# Encrypter.net
KiCad netlist of a schematic drawn in EAGLE
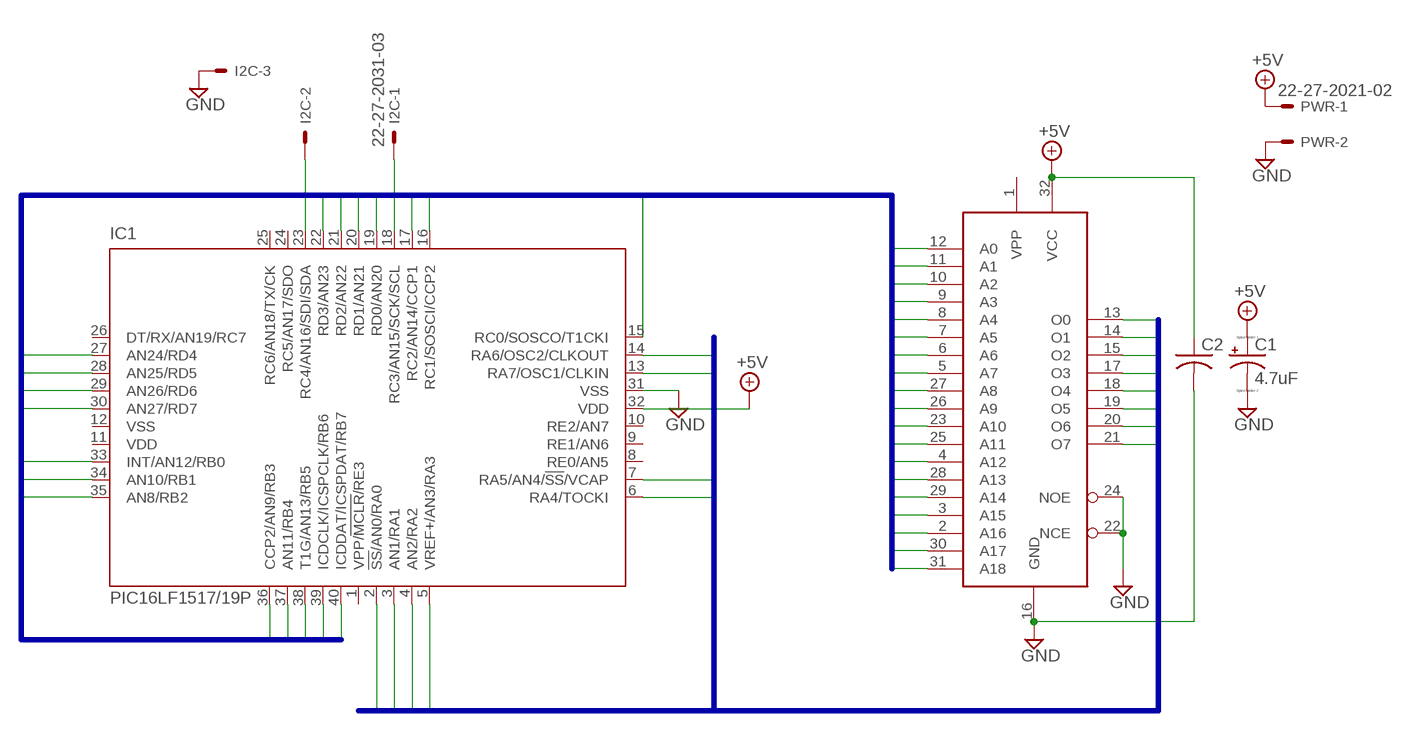
[diagram p0: schematic, sheet 1]

(export (version "E")
  (design (tool "Eeschema 10.0.6"))
  (components
    (comp (ref "C1")
      (value "4.7uF")
      (footprint "eagle-import:E3,5-10")
      (libsource (lib "eagle-import") (part "CPOL-USE3.5-10"))
    )
    (comp (ref "C2")
      (value "C-US050-025X075")
      (footprint "eagle-import:C050-025X075")
      (libsource (lib "eagle-import") (part "C-US050-025X075"))
    )
    (comp (ref "I2C")
      (value "22-27-2031-03")
      (footprint "eagle-import:6410-03")
      (libsource (lib "eagle-import") (part "22-?-0327-2031"))
    )
    (comp (ref "IC1")
      (value "PIC16LF1517/19P")
      (footprint "eagle-import:DIL40")
      (libsource (lib "eagle-import") (part "PIC16F1517/19PL"))
    )
    (comp (ref "PWR")
      (value "22-27-2021-02")
      (footprint "eagle-import:6410-02")
      (libsource (lib "eagle-import") (part "22-?-0227-2021"))
    )
    (comp (ref "U$1")
      (value "AT27C040")
      (footprint "eagle-import:DIL32")
      (libsource (lib "eagle-import") (part "AT27C040"))
    )
  )
  (nets
    (net (code "1") (name "+5V") (class "Default")
      (node (ref "C1") (pin "+") (pinfunction "+_+") (pintype "passive"))
      (node (ref "C2") (pin "1") (pinfunction "1_1") (pintype "passive"))
      (node (ref "IC1") (pin "32") (pinfunction "VDD_32") (pintype "power_in"))
      (node (ref "PWR") (pin "1") (pinfunction "S_1") (pintype "passive"))
      (node (ref "U$1") (pin "32") (pinfunction "VCC_32") (pintype "bidirectional"))
    )
    (net (code "2") (name "/A0") (class "Default")
      (node (ref "IC1") (pin "33") (pinfunction "INT/AN12/RB0_33") (pintype "bidirectional"))
      (node (ref "U$1") (pin "12") (pinfunction "A0_12") (pintype "bidirectional"))
    )
    (net (code "3") (name "/A1") (class "Default")
      (node (ref "IC1") (pin "34") (pinfunction "AN10/RB1_34") (pintype "bidirectional"))
      (node (ref "U$1") (pin "11") (pinfunction "A1_11") (pintype "bidirectional"))
    )
    (net (code "4") (name "/A2") (class "Default")
      (node (ref "IC1") (pin "35") (pinfunction "AN8/RB2_35") (pintype "bidirectional"))
      (node (ref "U$1") (pin "10") (pinfunction "A2_10") (pintype "bidirectional"))
    )
    (net (code "5") (name "/A3") (class "Default")
      (node (ref "IC1") (pin "36") (pinfunction "CCP2/AN9/RB3_36") (pintype "bidirectional"))
      (node (ref "U$1") (pin "9") (pinfunction "A3_9") (pintype "bidirectional"))
    )
    (net (code "6") (name "/A4") (class "Default")
      (node (ref "IC1") (pin "37") (pinfunction "AN11/RB4_37") (pintype "bidirectional"))
      (node (ref "U$1") (pin "8") (pinfunction "A4_8") (pintype "bidirectional"))
    )
    (net (code "7") (name "/A5") (class "Default")
      (node (ref "IC1") (pin "38") (pinfunction "T1G/AN13/RB5_38") (pintype "bidirectional"))
      (node (ref "U$1") (pin "7") (pinfunction "A5_7") (pintype "bidirectional"))
    )
    (net (code "8") (name "/A6") (class "Default")
      (node (ref "IC1") (pin "39") (pinfunction "ICDCLK/ICSPCLK/RB6_39") (pintype "bidirectional"))
      (node (ref "U$1") (pin "6") (pinfunction "A6_6") (pintype "bidirectional"))
    )
    (net (code "9") (name "/A7") (class "Default")
      (node (ref "IC1") (pin "40") (pinfunction "ICDDAT/ICSPDAT/RB7_40") (pintype "bidirectional"))
      (node (ref "U$1") (pin "5") (pinfunction "A7_5") (pintype "bidirectional"))
    )
    (net (code "10") (name "/A8") (class "Default")
      (node (ref "IC1") (pin "15") (pinfunction "RC0/SOSCO/T1CKI_15") (pintype "bidirectional"))
      (node (ref "U$1") (pin "27") (pinfunction "A8_27") (pintype "bidirectional"))
    )
    (net (code "11") (name "/A9") (class "Default")
      (node (ref "IC1") (pin "16") (pinfunction "RC1/SOSCI/CCP2_16") (pintype "bidirectional"))
      (node (ref "U$1") (pin "26") (pinfunction "A9_26") (pintype "bidirectional"))
    )
    (net (code "12") (name "/A10") (class "Default")
      (node (ref "IC1") (pin "17") (pinfunction "RC2/AN14/CCP1_17") (pintype "bidirectional"))
      (node (ref "U$1") (pin "23") (pinfunction "A10_23") (pintype "bidirectional"))
    )
    (net (code "13") (name "/A11") (class "Default")
      (node (ref "IC1") (pin "19") (pinfunction "RD0/AN20_19") (pintype "bidirectional"))
      (node (ref "U$1") (pin "25") (pinfunction "A11_25") (pintype "bidirectional"))
    )
    (net (code "14") (name "/A12") (class "Default")
      (node (ref "IC1") (pin "20") (pinfunction "RD1/AN21_20") (pintype "bidirectional"))
      (node (ref "U$1") (pin "4") (pinfunction "A12_4") (pintype "bidirectional"))
    )
    (net (code "15") (name "/A13") (class "Default")
      (node (ref "IC1") (pin "21") (pinfunction "RD2/AN22_21") (pintype "bidirectional"))
      (node (ref "U$1") (pin "28") (pinfunction "A13_28") (pintype "bidirectional"))
    )
    (net (code "16") (name "/A14") (class "Default")
      (node (ref "IC1") (pin "22") (pinfunction "RD3/AN23_22") (pintype "bidirectional"))
      (node (ref "U$1") (pin "29") (pinfunction "A14_29") (pintype "bidirectional"))
    )
    (net (code "17") (name "/A15") (class "Default")
      (node (ref "IC1") (pin "27") (pinfunction "AN24/RD4_27") (pintype "bidirectional"))
      (node (ref "U$1") (pin "3") (pinfunction "A15_3") (pintype "bidirectional"))
    )
    (net (code "18") (name "/A16") (class "Default")
      (node (ref "IC1") (pin "28") (pinfunction "AN25/RD5_28") (pintype "bidirectional"))
      (node (ref "U$1") (pin "2") (pinfunction "A16_2") (pintype "bidirectional"))
    )
    (net (code "19") (name "/A17") (class "Default")
      (node (ref "IC1") (pin "29") (pinfunction "AN26/RD6_29") (pintype "bidirectional"))
      (node (ref "U$1") (pin "30") (pinfunction "A17_30") (pintype "bidirectional"))
    )
    (net (code "20") (name "/A18") (class "Default")
      (node (ref "IC1") (pin "30") (pinfunction "AN27/RD7_30") (pintype "bidirectional"))
      (node (ref "U$1") (pin "31") (pinfunction "A18_31") (pintype "bidirectional"))
    )
    (net (code "21") (name "/O0") (class "Default")
      (node (ref "IC1") (pin "2") (pinfunction "~{SS}/AN0/RA0_2") (pintype "bidirectional"))
      (node (ref "U$1") (pin "13") (pinfunction "O0_13") (pintype "output"))
    )
    (net (code "22") (name "/O1") (class "Default")
      (node (ref "IC1") (pin "3") (pinfunction "AN1/RA1_3") (pintype "bidirectional"))
      (node (ref "U$1") (pin "14") (pinfunction "O1_14") (pintype "output"))
    )
    (net (code "23") (name "/O2") (class "Default")
      (node (ref "IC1") (pin "4") (pinfunction "AN2/RA2_4") (pintype "bidirectional"))
      (node (ref "U$1") (pin "15") (pinfunction "O2_15") (pintype "output"))
    )
    (net (code "24") (name "/O3") (class "Default")
      (node (ref "IC1") (pin "5") (pinfunction "VREF+/AN3/RA3_5") (pintype "bidirectional"))
      (node (ref "U$1") (pin "17") (pinfunction "O3_17") (pintype "output"))
    )
    (net (code "25") (name "/O4") (class "Default")
      (node (ref "IC1") (pin "6") (pinfunction "RA4/TOCKI_6") (pintype "bidirectional"))
      (node (ref "U$1") (pin "18") (pinfunction "O4_18") (pintype "output"))
    )
    (net (code "26") (name "/O5") (class "Default")
      (node (ref "IC1") (pin "7") (pinfunction "RA5/AN4/~{SS}/VCAP_7") (pintype "bidirectional"))
      (node (ref "U$1") (pin "19") (pinfunction "O5_19") (pintype "output"))
    )
    (net (code "27") (name "/O6") (class "Default")
      (node (ref "IC1") (pin "14") (pinfunction "RA6/OSC2/CLKOUT_14") (pintype "bidirectional"))
      (node (ref "U$1") (pin "20") (pinfunction "O6_20") (pintype "output"))
    )
    (net (code "28") (name "/O7") (class "Default")
      (node (ref "IC1") (pin "13") (pinfunction "RA7/OSC1/CLKIN_13") (pintype "bidirectional"))
      (node (ref "U$1") (pin "21") (pinfunction "O7_21") (pintype "output"))
    )
    (net (code "29") (name "/VDD") (class "Default")
      (node (ref "IC1") (pin "11") (pinfunction "VDD_11") (pintype "power_in"))
    )
    (net (code "30") (name "/VSS") (class "Default")
      (node (ref "IC1") (pin "12") (pinfunction "VSS_12") (pintype "power_in"))
    )
    (net (code "31") (name "GND") (class "Default")
      (node (ref "C1") (pin "-") (pinfunction "-_-") (pintype "passive"))
      (node (ref "C2") (pin "2") (pinfunction "2_2") (pintype "passive"))
      (node (ref "I2C") (pin "3") (pinfunction "S_3") (pintype "passive"))
      (node (ref "IC1") (pin "31") (pinfunction "VSS_31") (pintype "power_in"))
      (node (ref "PWR") (pin "2") (pinfunction "S_2") (pintype "passive"))
      (node (ref "U$1") (pin "16") (pinfunction "GND_16") (pintype "bidirectional"))
      (node (ref "U$1") (pin "22") (pinfunction "NCE_22") (pintype "bidirectional"))
      (node (ref "U$1") (pin "24") (pinfunction "NOE_24") (pintype "bidirectional"))
    )
    (net (code "32") (name "Net-(I2CA-S)") (class "Default")
      (node (ref "I2C") (pin "1") (pinfunction "S_1") (pintype "passive"))
      (node (ref "IC1") (pin "18") (pinfunction "RC3/AN15/SCK/SCL_18") (pintype "bidirectional"))
    )
    (net (code "33") (name "Net-(I2CB-S)") (class "Default")
      (node (ref "I2C") (pin "2") (pinfunction "S_2") (pintype "passive"))
      (node (ref "IC1") (pin "23") (pinfunction "RC4/AN16/SDI/SDA_23") (pintype "bidirectional"))
    )
    (net (code "34") (name "unconnected-(IC1-DT{slash}RX{slash}AN19{slash}RC7-Pad26)") (class "Default")
      (node (ref "IC1") (pin "26") (pinfunction "DT/RX/AN19/RC7_26") (pintype "bidirectional"))
    )
    (net (code "35") (name "unconnected-(IC1-RC5{slash}AN17{slash}SDO-Pad24)") (class "Default")
      (node (ref "IC1") (pin "24") (pinfunction "RC5/AN17/SDO_24") (pintype "bidirectional"))
    )
    (net (code "36") (name "unconnected-(IC1-RC6{slash}AN18{slash}TX{slash}CK-Pad25)") (class "Default")
      (node (ref "IC1") (pin "25") (pinfunction "RC6/AN18/TX/CK_25") (pintype "bidirectional"))
    )
    (net (code "37") (name "unconnected-(IC1-RE0{slash}AN5-Pad8)") (class "Default")
      (node (ref "IC1") (pin "8") (pinfunction "RE0/AN5_8") (pintype "bidirectional"))
    )
    (net (code "38") (name "unconnected-(IC1-RE1{slash}AN6-Pad9)") (class "Default")
      (node (ref "IC1") (pin "9") (pinfunction "RE1/AN6_9") (pintype "bidirectional"))
    )
    (net (code "39") (name "unconnected-(IC1-RE2{slash}AN7-Pad10)") (class "Default")
      (node (ref "IC1") (pin "10") (pinfunction "RE2/AN7_10") (pintype "bidirectional"))
    )
    (net (code "40") (name "unconnected-(IC1-VPP{slash}~{MCLR}{slash}RE3-Pad1)") (class "Default")
      (node (ref "IC1") (pin "1") (pinfunction "VPP/~{MCLR}/RE3_1") (pintype "input"))
    )
    (net (code "41") (name "unconnected-(U$1-VPP-Pad1)") (class "Default")
      (node (ref "U$1") (pin "1") (pinfunction "VPP_1") (pintype "bidirectional"))
    )
  )
)
